# DCDC_pump.net
KiCad netlist of a schematic drawn in Altium Designer
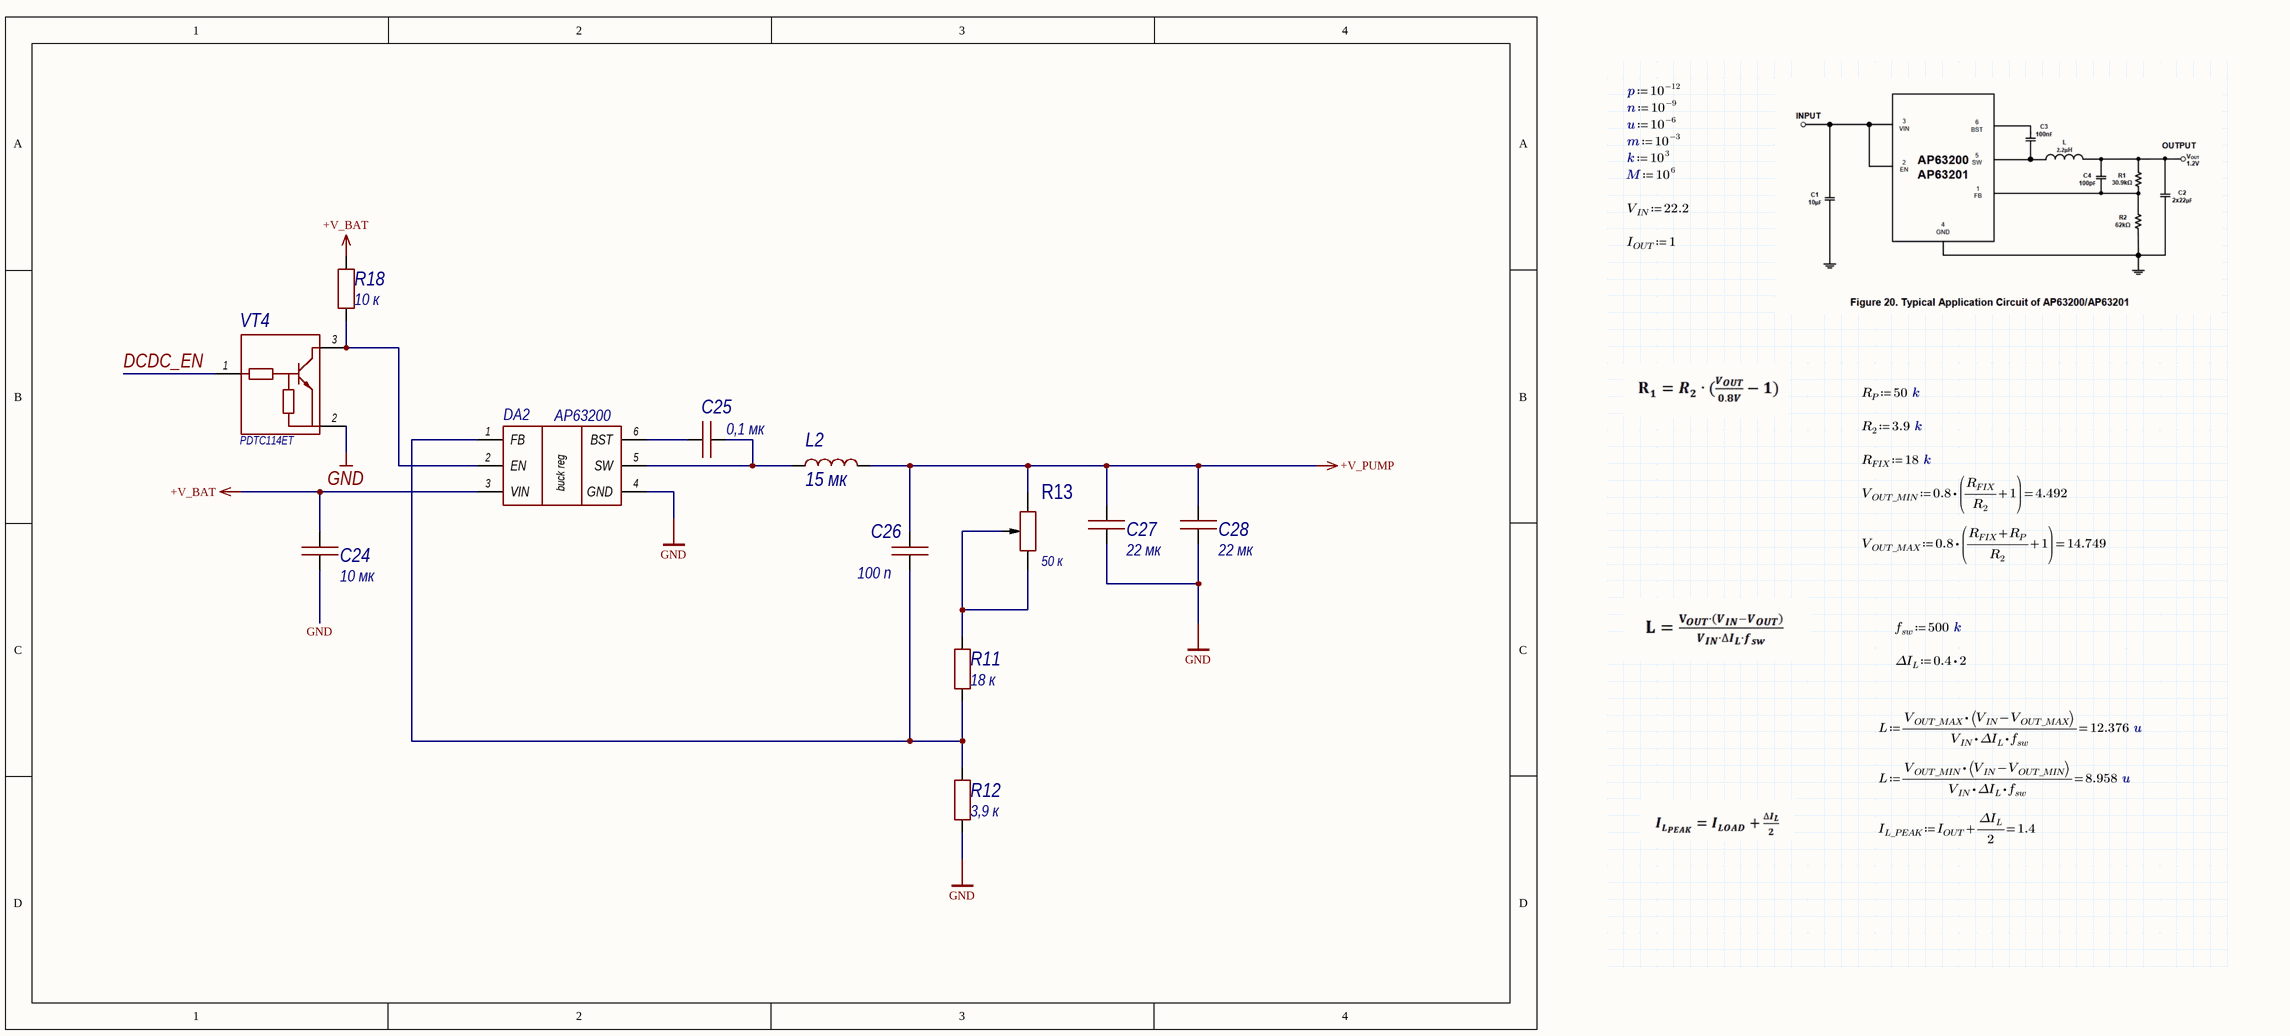
[diagram p0: DCDC_pump.SchDoc]

(export (version "E")
  (design (tool "Eeschema 10.0.6"))
  (components
    (comp (ref "C24")
      (value "10 мк")
      (footprint "1210C")
      (description "Конденсатор")
      (fields (field (name "PART NUMBER") "Capacitor_10u_10_35V_X7R_1210C") (field (name "TOLERANCE") "0,1"))
      (libsource (lib "Hydrolib") (part "Capacitor"))
    )
    (comp (ref "C25")
      (value "0,1 мк")
      (footprint "0603C")
      (description "Конденсатор")
      (fields (field (name "PART NUMBER") "Capacitor_0,1u_10_50V_X7R_0603C") (field (name "TOLERANCE") "0,1"))
      (libsource (lib "Hydrolib") (part "Capacitor"))
    )
    (comp (ref "C26")
      (value "100 п")
      (footprint "0603C")
      (description "Конденсатор")
      (fields (field (name "PART NUMBER") "Capacitor_100p_10_50V_X7R_0603C") (field (name "TOLERANCE") "0,1"))
      (libsource (lib "Hydrolib") (part "Capacitor"))
    )
    (comp (ref "C27")
      (value "22 мк")
      (footprint "1210C")
      (description "Конденсатор")
      (fields (field (name "PART NUMBER") "Capacitor_22u_10_25V_X7R_1210C") (field (name "TOLERANCE") "0,1"))
      (libsource (lib "Hydrolib") (part "Capacitor"))
    )
    (comp (ref "C28")
      (value "22 мк")
      (footprint "1210C")
      (description "Конденсатор")
      (fields (field (name "PART NUMBER") "Capacitor_22u_10_25V_X7R_1210C") (field (name "TOLERANCE") "0,1"))
      (libsource (lib "Hydrolib") (part "Capacitor"))
    )
    (comp (ref "DA2")
      (value "AP63200")
      (footprint "TSOT26")
      (description "DC-DC понижающий преобразователь, Vin: 3.8 - 40 В, adj, 2 А")
      (libsource (lib "Hydrolib") (part "AP63200"))
    )
    (comp (ref "L2")
      (value "15 мк")
      (footprint "SP43")
      (description "Индуктивность на 15 мкГн, номинальный ток 1,3 А")
      (fields (field (name "PART NUMBER") "SP43-150K"))
      (libsource (lib "Hydrolib") (part "Inductance"))
    )
    (comp (ref "R11")
      (value "18 к")
      (footprint "0603R")
      (description "Резистор номиналом 18 кОм и точностью 1%")
      (fields (field (name "PART NUMBER") "Resistor_18k_1_0603") (field (name "TOLERANCE") "1%"))
      (libsource (lib "Hydrolib") (part "Resistor"))
    )
    (comp (ref "R12")
      (value "3,9 к")
      (footprint "0603R")
      (description "Резистор номиналом 3,9 кОм и точностью 1%")
      (fields (field (name "PART NUMBER") "Resistor_3.9k_1_0603") (field (name "TOLERANCE") "1%"))
      (libsource (lib "Hydrolib") (part "Resistor"))
    )
    (comp (ref "R13")
      (value "50 к")
      (footprint "3mm_trim")
      (description "Потенциометр однооборотный керметный 50кОм 0.1Вт ±25% SMD лента на катушке")
      (fields (field (name "PART NUMBER") "TC33X-2-503E") (field (name "TOLERANCE") "50%"))
      (libsource (lib "Hydrolib") (part "trim_res"))
    )
    (comp (ref "R18")
      (value "10 к")
      (footprint "0603R")
      (description "Резистор номиналом 10 кОм 1%")
      (fields (field (name "PART NUMBER") "Resistor_10k_1_0603") (field (name "TOLERANCE") "1%"))
      (libsource (lib "Hydrolib") (part "Resistor"))
    )
    (comp (ref "VT4")
      (value "PDTC114ET")
      (footprint "SOT23-3")
      (description "цифровой npn 50в 100мА")
      (libsource (lib "Hydrolib") (part "PDTC114ET"))
    )
  )
  (nets
    (net (code "1") (name "+V_BAT") (class "Default")
      (node (ref "C24") (pin "2") (pinfunction "2_2") (pintype "passive"))
      (node (ref "DA2") (pin "3") (pinfunction "VIN_3") (pintype "passive"))
      (node (ref "R18") (pin "2") (pinfunction "2_2") (pintype "passive"))
    )
    (net (code "2") (name "+V_PUMP") (class "Default")
      (node (ref "C26") (pin "2") (pinfunction "2_2") (pintype "passive"))
      (node (ref "C27") (pin "2") (pinfunction "2_2") (pintype "passive"))
      (node (ref "C28") (pin "2") (pinfunction "2_2") (pintype "passive"))
      (node (ref "L2") (pin "2") (pinfunction "2_2") (pintype "passive"))
      (node (ref "R13") (pin "3") (pinfunction "3_3") (pintype "passive"))
    )
    (net (code "3") (name "/DCDC_EN") (class "Default")
      (node (ref "VT4") (pin "1") (pinfunction "B_1") (pintype "passive"))
    )
    (net (code "4") (name "GND") (class "Default")
      (node (ref "C24") (pin "1") (pinfunction "1_1") (pintype "passive"))
      (node (ref "C27") (pin "1") (pinfunction "1_1") (pintype "passive"))
      (node (ref "C28") (pin "1") (pinfunction "1_1") (pintype "passive"))
      (node (ref "DA2") (pin "4") (pinfunction "GND_4") (pintype "passive"))
      (node (ref "R12") (pin "1") (pinfunction "1_1") (pintype "passive"))
      (node (ref "VT4") (pin "2") (pinfunction "E_2") (pintype "passive"))
    )
    (net (code "5") (name "Net-(DA2-BST)") (class "Default")
      (node (ref "C25") (pin "1") (pinfunction "1_1") (pintype "passive"))
      (node (ref "DA2") (pin "6") (pinfunction "BST_6") (pintype "passive"))
    )
    (net (code "6") (name "Net-(DA2-EN)") (class "Default")
      (node (ref "DA2") (pin "2") (pinfunction "EN_2") (pintype "passive"))
      (node (ref "R18") (pin "1") (pinfunction "1_1") (pintype "passive"))
      (node (ref "VT4") (pin "3") (pinfunction "C_3") (pintype "passive"))
    )
    (net (code "7") (name "Net-(DA2-FB)") (class "Default")
      (node (ref "C26") (pin "1") (pinfunction "1_1") (pintype "passive"))
      (node (ref "DA2") (pin "1") (pinfunction "FB_1") (pintype "passive"))
      (node (ref "R11") (pin "1") (pinfunction "1_1") (pintype "passive"))
      (node (ref "R12") (pin "2") (pinfunction "2_2") (pintype "passive"))
    )
    (net (code "8") (name "Net-(DA2-SW)") (class "Default")
      (node (ref "C25") (pin "2") (pinfunction "2_2") (pintype "passive"))
      (node (ref "DA2") (pin "5") (pinfunction "SW_5") (pintype "passive"))
      (node (ref "L2") (pin "1") (pinfunction "1_1") (pintype "passive"))
    )
    (net (code "9") (name "Net-(R11-Pad2)") (class "Default")
      (node (ref "R11") (pin "2") (pinfunction "2_2") (pintype "passive"))
      (node (ref "R13") (pin "1") (pinfunction "1_1") (pintype "passive"))
      (node (ref "R13") (pin "2") (pinfunction "2_2") (pintype "passive"))
    )
  )
)
